# quadcopter_sch.net
KiCad netlist of a schematic drawn in EAGLE
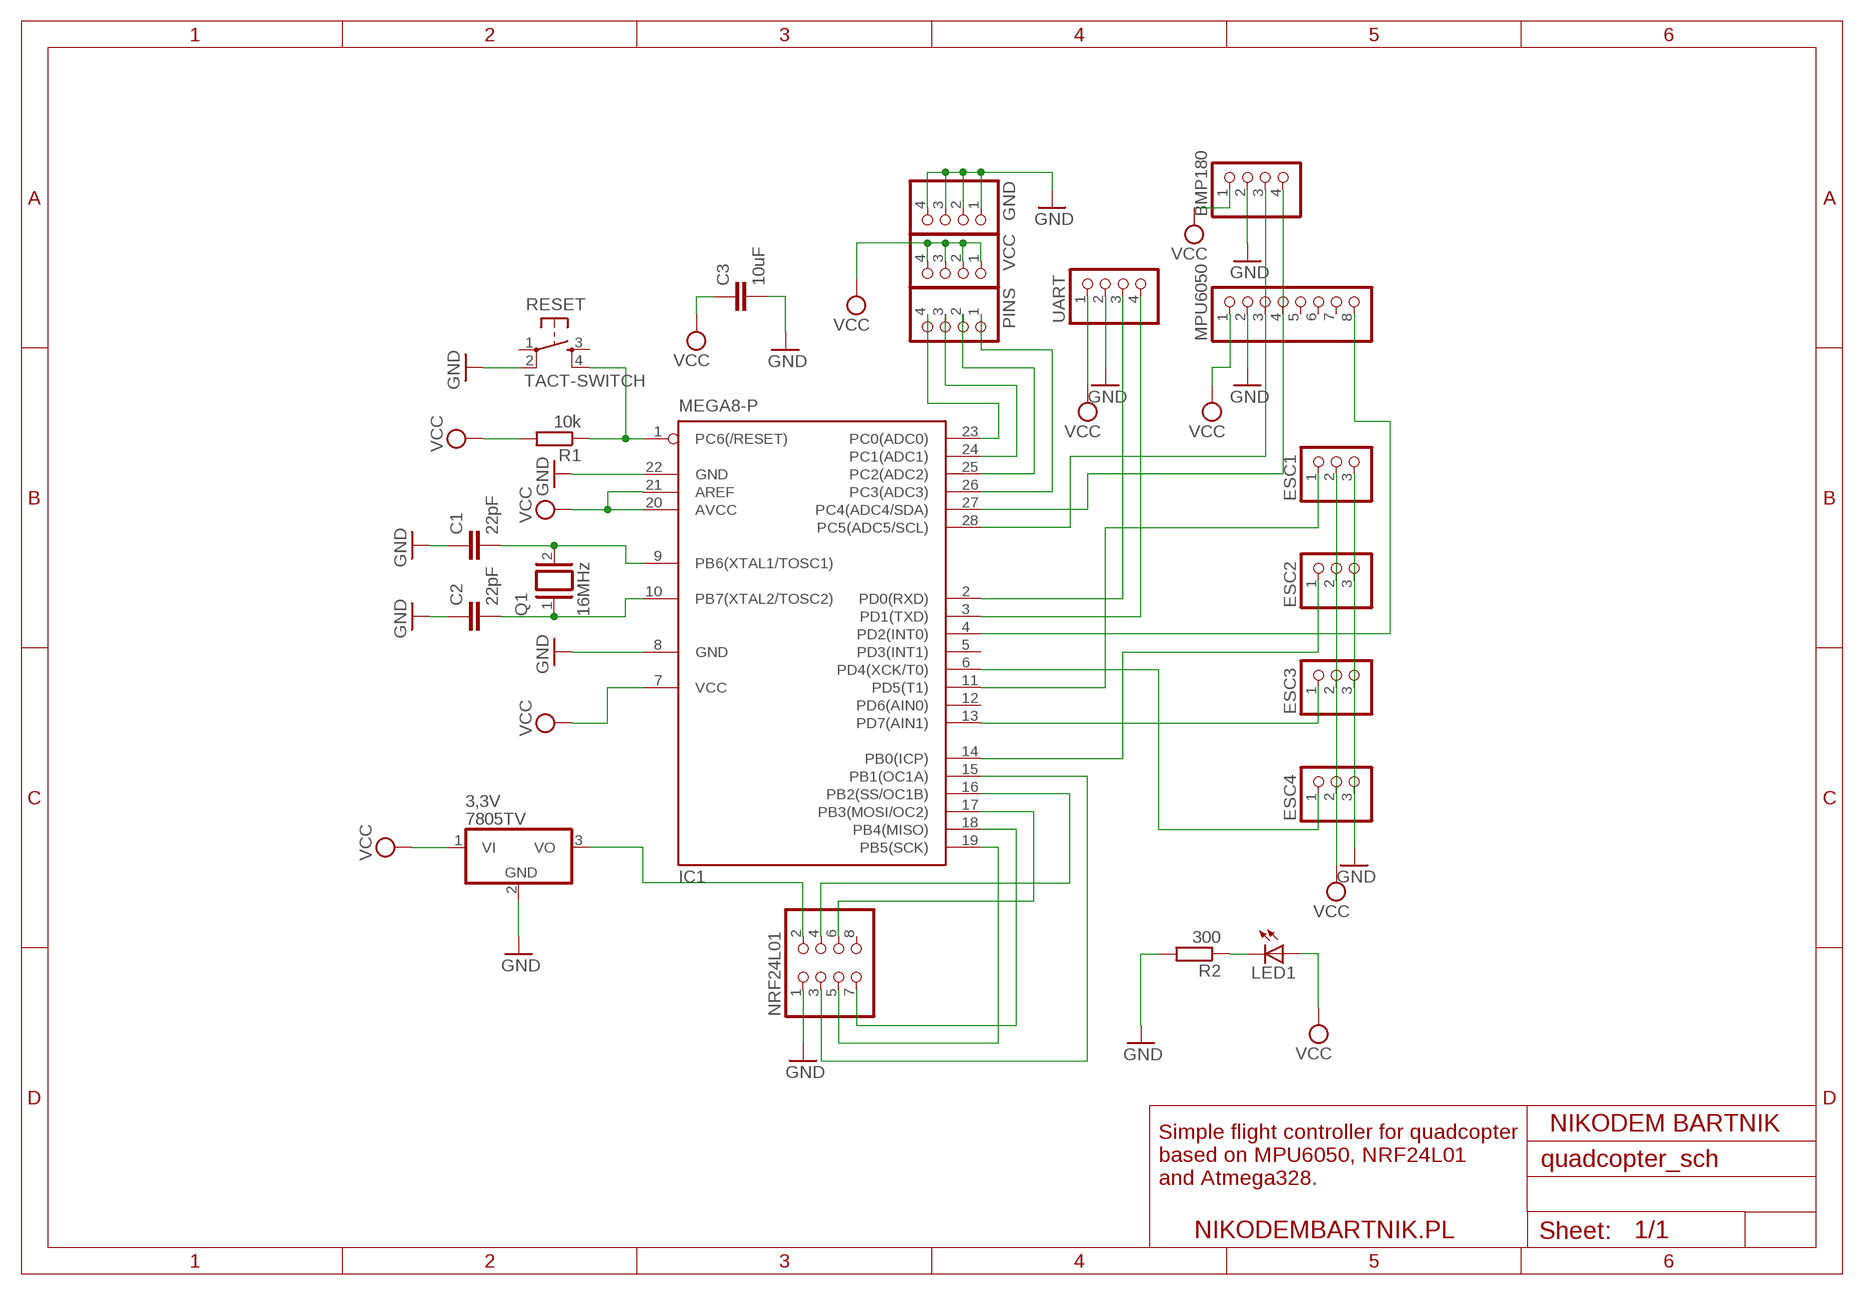
[diagram p0: schematic, sheet 1]

(export (version "E")
  (design (tool "Eeschema 10.0.6"))
  (components
    (comp (ref "3,3V")
      (value "7805TV")
      (footprint "eagle-import:TO220V")
      (libsource (lib "eagle-import") (part "78TV05"))
    )
    (comp (ref "BMP180")
      (value "PINHD-1X4")
      (footprint "eagle-import:1X04")
      (libsource (lib "eagle-import") (part "PINHD-1X4"))
    )
    (comp (ref "C1")
      (value "22pF")
      (footprint "eagle-import:C2.5-3")
      (libsource (lib "eagle-import") (part "C2,5-3"))
    )
    (comp (ref "C2")
      (value "22pF")
      (footprint "eagle-import:C2.5-3")
      (libsource (lib "eagle-import") (part "C2,5-3"))
    )
    (comp (ref "C3")
      (value "10uF")
      (footprint "eagle-import:C2.5-3")
      (libsource (lib "eagle-import") (part "C2,5-3"))
    )
    (comp (ref "ESC1")
      (value "PINHD-1X3")
      (footprint "eagle-import:1X03")
      (libsource (lib "eagle-import") (part "PINHD-1X3"))
    )
    (comp (ref "ESC2")
      (value "PINHD-1X3")
      (footprint "eagle-import:1X03")
      (libsource (lib "eagle-import") (part "PINHD-1X3"))
    )
    (comp (ref "ESC3")
      (value "PINHD-1X3")
      (footprint "eagle-import:1X03")
      (libsource (lib "eagle-import") (part "PINHD-1X3"))
    )
    (comp (ref "ESC4")
      (value "PINHD-1X3")
      (footprint "eagle-import:1X03")
      (libsource (lib "eagle-import") (part "PINHD-1X3"))
    )
    (comp (ref "GND")
      (value "PINHD-1X4")
      (footprint "eagle-import:1X04")
      (libsource (lib "eagle-import") (part "PINHD-1X4"))
    )
    (comp (ref "IC1")
      (value "MEGA8-P")
      (footprint "eagle-import:DIL28-3")
      (libsource (lib "eagle-import") (part "MEGA8-P"))
    )
    (comp (ref "LED1")
      (value "LED5MM")
      (footprint "eagle-import:LED5MM")
      (libsource (lib "eagle-import") (part "LED5MM"))
    )
    (comp (ref "MPU6050")
      (value "PINHD-1X8")
      (footprint "eagle-import:1X08")
      (libsource (lib "eagle-import") (part "PINHD-1X8"))
    )
    (comp (ref "NRF24L01")
      (value "PINHD-2X4")
      (footprint "eagle-import:2X04")
      (libsource (lib "eagle-import") (part "PINHD-2X4"))
    )
    (comp (ref "PINS")
      (value "PINHD-1X4")
      (footprint "eagle-import:1X04")
      (libsource (lib "eagle-import") (part "PINHD-1X4"))
    )
    (comp (ref "Q1")
      (value "16MHz")
      (footprint "eagle-import:QS")
      (libsource (lib "eagle-import") (part "XTAL/S"))
    )
    (comp (ref "R1")
      (value "10k")
      (footprint "eagle-import:0204V")
      (libsource (lib "eagle-import") (part "R-EU_0204/2V"))
    )
    (comp (ref "R2")
      (value "300")
      (footprint "eagle-import:0204V")
      (libsource (lib "eagle-import") (part "R-EU_0204/2V"))
    )
    (comp (ref "RESET")
      (value "TACT-SWITCH")
      (footprint "eagle-import:TAC-SWITCH-PTH")
      (libsource (lib "eagle-import") (part "TACTILE-SWITCH-PTH"))
    )
    (comp (ref "UART")
      (value "PINHD-1X4")
      (footprint "eagle-import:1X04")
      (libsource (lib "eagle-import") (part "PINHD-1X4"))
    )
    (comp (ref "VCC")
      (value "PINHD-1X4")
      (footprint "eagle-import:1X04")
      (libsource (lib "eagle-import") (part "PINHD-1X4"))
    )
  )
  (nets
    (net (code "1") (name "GND") (class "Default")
      (node (ref "3,3V") (pin "2") (pinfunction "GND_2") (pintype "passive"))
      (node (ref "BMP180") (pin "2") (pinfunction "2_2") (pintype "passive"))
      (node (ref "C1") (pin "1") (pinfunction "1_1") (pintype "passive"))
      (node (ref "C2") (pin "1") (pinfunction "1_1") (pintype "passive"))
      (node (ref "C3") (pin "2") (pinfunction "2_2") (pintype "passive"))
      (node (ref "ESC1") (pin "3") (pinfunction "3_3") (pintype "passive"))
      (node (ref "ESC2") (pin "3") (pinfunction "3_3") (pintype "passive"))
      (node (ref "ESC3") (pin "3") (pinfunction "3_3") (pintype "passive"))
      (node (ref "ESC4") (pin "3") (pinfunction "3_3") (pintype "passive"))
      (node (ref "GND") (pin "1") (pinfunction "1_1") (pintype "passive"))
      (node (ref "GND") (pin "2") (pinfunction "2_2") (pintype "passive"))
      (node (ref "GND") (pin "3") (pinfunction "3_3") (pintype "passive"))
      (node (ref "GND") (pin "4") (pinfunction "4_4") (pintype "passive"))
      (node (ref "IC1") (pin "22") (pinfunction "GND_22") (pintype "power_in"))
      (node (ref "IC1") (pin "8") (pinfunction "GND_8") (pintype "power_in"))
      (node (ref "MPU6050") (pin "2") (pinfunction "2_2") (pintype "passive"))
      (node (ref "NRF24L01") (pin "1") (pinfunction "1_1") (pintype "passive"))
      (node (ref "R2") (pin "2") (pinfunction "2_2") (pintype "passive"))
      (node (ref "RESET") (pin "2") (pinfunction "2_2") (pintype "passive"))
      (node (ref "UART") (pin "2") (pinfunction "2_2") (pintype "passive"))
    )
    (net (code "2") (name "Net-(3,3V-VO)") (class "Default")
      (node (ref "3,3V") (pin "3") (pinfunction "VO_3") (pintype "passive"))
      (node (ref "NRF24L01") (pin "2") (pinfunction "2_2") (pintype "passive"))
    )
    (net (code "3") (name "Net-(IC1-PB0(ICP))") (class "Default")
      (node (ref "ESC2") (pin "1") (pinfunction "1_1") (pintype "passive"))
      (node (ref "IC1") (pin "14") (pinfunction "PB0(ICP)_14") (pintype "bidirectional"))
    )
    (net (code "4") (name "Net-(IC1-PB1(OC1A))") (class "Default")
      (node (ref "IC1") (pin "15") (pinfunction "PB1(OC1A)_15") (pintype "bidirectional"))
      (node (ref "NRF24L01") (pin "3") (pinfunction "3_3") (pintype "passive"))
    )
    (net (code "5") (name "Net-(IC1-PB2(SS{slash}OC1B))") (class "Default")
      (node (ref "IC1") (pin "16") (pinfunction "PB2(SS/OC1B)_16") (pintype "bidirectional"))
      (node (ref "NRF24L01") (pin "4") (pinfunction "4_4") (pintype "passive"))
    )
    (net (code "6") (name "Net-(IC1-PB3(MOSI{slash}OC2))") (class "Default")
      (node (ref "IC1") (pin "17") (pinfunction "PB3(MOSI/OC2)_17") (pintype "bidirectional"))
      (node (ref "NRF24L01") (pin "6") (pinfunction "6_6") (pintype "passive"))
    )
    (net (code "7") (name "Net-(IC1-PB4(MISO))") (class "Default")
      (node (ref "IC1") (pin "18") (pinfunction "PB4(MISO)_18") (pintype "bidirectional"))
      (node (ref "NRF24L01") (pin "7") (pinfunction "7_7") (pintype "passive"))
    )
    (net (code "8") (name "Net-(IC1-PB5(SCK))") (class "Default")
      (node (ref "IC1") (pin "19") (pinfunction "PB5(SCK)_19") (pintype "bidirectional"))
      (node (ref "NRF24L01") (pin "5") (pinfunction "5_5") (pintype "passive"))
    )
    (net (code "9") (name "Net-(IC1-PB6(XTAL1{slash}TOSC1))") (class "Default")
      (node (ref "C1") (pin "2") (pinfunction "2_2") (pintype "passive"))
      (node (ref "IC1") (pin "9") (pinfunction "PB6(XTAL1/TOSC1)_9") (pintype "bidirectional"))
      (node (ref "Q1") (pin "2") (pinfunction "2_2") (pintype "passive"))
    )
    (net (code "10") (name "Net-(IC1-PB7(XTAL2{slash}TOSC2))") (class "Default")
      (node (ref "C2") (pin "2") (pinfunction "2_2") (pintype "passive"))
      (node (ref "IC1") (pin "10") (pinfunction "PB7(XTAL2/TOSC2)_10") (pintype "bidirectional"))
      (node (ref "Q1") (pin "1") (pinfunction "1_1") (pintype "passive"))
    )
    (net (code "11") (name "Net-(IC1-PC0(ADC0))") (class "Default")
      (node (ref "IC1") (pin "23") (pinfunction "PC0(ADC0)_23") (pintype "bidirectional"))
      (node (ref "PINS") (pin "4") (pinfunction "4_4") (pintype "passive"))
    )
    (net (code "12") (name "Net-(IC1-PC1(ADC1))") (class "Default")
      (node (ref "IC1") (pin "24") (pinfunction "PC1(ADC1)_24") (pintype "bidirectional"))
      (node (ref "PINS") (pin "3") (pinfunction "3_3") (pintype "passive"))
    )
    (net (code "13") (name "Net-(IC1-PC2(ADC2))") (class "Default")
      (node (ref "IC1") (pin "25") (pinfunction "PC2(ADC2)_25") (pintype "bidirectional"))
      (node (ref "PINS") (pin "2") (pinfunction "2_2") (pintype "passive"))
    )
    (net (code "14") (name "Net-(IC1-PC3(ADC3))") (class "Default")
      (node (ref "IC1") (pin "26") (pinfunction "PC3(ADC3)_26") (pintype "bidirectional"))
      (node (ref "PINS") (pin "1") (pinfunction "1_1") (pintype "passive"))
    )
    (net (code "15") (name "Net-(IC1-PC4(ADC4{slash}SDA))") (class "Default")
      (node (ref "BMP180") (pin "4") (pinfunction "4_4") (pintype "passive"))
      (node (ref "IC1") (pin "27") (pinfunction "PC4(ADC4/SDA)_27") (pintype "bidirectional"))
      (node (ref "MPU6050") (pin "4") (pinfunction "4_4") (pintype "passive"))
    )
    (net (code "16") (name "Net-(IC1-PC5(ADC5{slash}SCL))") (class "Default")
      (node (ref "BMP180") (pin "3") (pinfunction "3_3") (pintype "passive"))
      (node (ref "IC1") (pin "28") (pinfunction "PC5(ADC5/SCL)_28") (pintype "bidirectional"))
      (node (ref "MPU6050") (pin "3") (pinfunction "3_3") (pintype "passive"))
    )
    (net (code "17") (name "Net-(IC1-PC6({slash}RESET))") (class "Default")
      (node (ref "IC1") (pin "1") (pinfunction "PC6(/RESET)_1") (pintype "bidirectional"))
      (node (ref "R1") (pin "1") (pinfunction "1_1") (pintype "passive"))
      (node (ref "RESET") (pin "4") (pinfunction "4_4") (pintype "passive"))
    )
    (net (code "18") (name "Net-(IC1-PD0(RXD))") (class "Default")
      (node (ref "IC1") (pin "2") (pinfunction "PD0(RXD)_2") (pintype "bidirectional"))
      (node (ref "UART") (pin "3") (pinfunction "3_3") (pintype "passive"))
    )
    (net (code "19") (name "Net-(IC1-PD1(TXD))") (class "Default")
      (node (ref "IC1") (pin "3") (pinfunction "PD1(TXD)_3") (pintype "bidirectional"))
      (node (ref "UART") (pin "4") (pinfunction "4_4") (pintype "passive"))
    )
    (net (code "20") (name "Net-(IC1-PD2(INT0))") (class "Default")
      (node (ref "IC1") (pin "4") (pinfunction "PD2(INT0)_4") (pintype "bidirectional"))
      (node (ref "MPU6050") (pin "8") (pinfunction "8_8") (pintype "passive"))
    )
    (net (code "21") (name "Net-(IC1-PD4(XCK{slash}T0))") (class "Default")
      (node (ref "ESC4") (pin "1") (pinfunction "1_1") (pintype "passive"))
      (node (ref "IC1") (pin "6") (pinfunction "PD4(XCK/T0)_6") (pintype "bidirectional"))
    )
    (net (code "22") (name "Net-(IC1-PD5(T1))") (class "Default")
      (node (ref "ESC1") (pin "1") (pinfunction "1_1") (pintype "passive"))
      (node (ref "IC1") (pin "11") (pinfunction "PD5(T1)_11") (pintype "bidirectional"))
    )
    (net (code "23") (name "Net-(IC1-PD7(AIN1))") (class "Default")
      (node (ref "ESC3") (pin "1") (pinfunction "1_1") (pintype "passive"))
      (node (ref "IC1") (pin "13") (pinfunction "PD7(AIN1)_13") (pintype "bidirectional"))
    )
    (net (code "24") (name "Net-(LED1-C)") (class "Default")
      (node (ref "LED1") (pin "K") (pinfunction "C_K") (pintype "passive"))
      (node (ref "R2") (pin "1") (pinfunction "1_1") (pintype "passive"))
    )
    (net (code "25") (name "VCC") (class "Default")
      (node (ref "3,3V") (pin "1") (pinfunction "VI_1") (pintype "input"))
      (node (ref "BMP180") (pin "1") (pinfunction "1_1") (pintype "passive"))
      (node (ref "C3") (pin "1") (pinfunction "1_1") (pintype "passive"))
      (node (ref "ESC1") (pin "2") (pinfunction "2_2") (pintype "passive"))
      (node (ref "ESC2") (pin "2") (pinfunction "2_2") (pintype "passive"))
      (node (ref "ESC3") (pin "2") (pinfunction "2_2") (pintype "passive"))
      (node (ref "ESC4") (pin "2") (pinfunction "2_2") (pintype "passive"))
      (node (ref "IC1") (pin "20") (pinfunction "AVCC_20") (pintype "power_in"))
      (node (ref "IC1") (pin "21") (pinfunction "AREF_21") (pintype "passive"))
      (node (ref "IC1") (pin "7") (pinfunction "VCC_7") (pintype "power_in"))
      (node (ref "LED1") (pin "A") (pinfunction "A_A") (pintype "passive"))
      (node (ref "MPU6050") (pin "1") (pinfunction "1_1") (pintype "passive"))
      (node (ref "R1") (pin "2") (pinfunction "2_2") (pintype "passive"))
      (node (ref "UART") (pin "1") (pinfunction "1_1") (pintype "passive"))
      (node (ref "VCC") (pin "1") (pinfunction "1_1") (pintype "passive"))
      (node (ref "VCC") (pin "2") (pinfunction "2_2") (pintype "passive"))
      (node (ref "VCC") (pin "3") (pinfunction "3_3") (pintype "passive"))
      (node (ref "VCC") (pin "4") (pinfunction "4_4") (pintype "passive"))
    )
    (net (code "26") (name "unconnected-(IC1-PD3(INT1)-Pad5)") (class "Default")
      (node (ref "IC1") (pin "5") (pinfunction "PD3(INT1)_5") (pintype "bidirectional"))
    )
    (net (code "27") (name "unconnected-(IC1-PD6(AIN0)-Pad12)") (class "Default")
      (node (ref "IC1") (pin "12") (pinfunction "PD6(AIN0)_12") (pintype "bidirectional"))
    )
    (net (code "28") (name "unconnected-(MPU6050-Pad5)") (class "Default")
      (node (ref "MPU6050") (pin "5") (pinfunction "5_5") (pintype "passive"))
    )
    (net (code "29") (name "unconnected-(MPU6050-Pad6)") (class "Default")
      (node (ref "MPU6050") (pin "6") (pinfunction "6_6") (pintype "passive"))
    )
    (net (code "30") (name "unconnected-(MPU6050-Pad7)") (class "Default")
      (node (ref "MPU6050") (pin "7") (pinfunction "7_7") (pintype "passive"))
    )
    (net (code "31") (name "unconnected-(NRF24L01-Pad8)") (class "Default")
      (node (ref "NRF24L01") (pin "8") (pinfunction "8_8") (pintype "passive"))
    )
    (net (code "32") (name "unconnected-(RESET-Pad1)") (class "Default")
      (node (ref "RESET") (pin "1") (pinfunction "1_1") (pintype "passive"))
    )
    (net (code "33") (name "unconnected-(RESET-Pad3)") (class "Default")
      (node (ref "RESET") (pin "3") (pinfunction "3_3") (pintype "passive"))
    )
  )
)
